# Board_R2.net
KiCad netlist of a schematic drawn in EAGLE
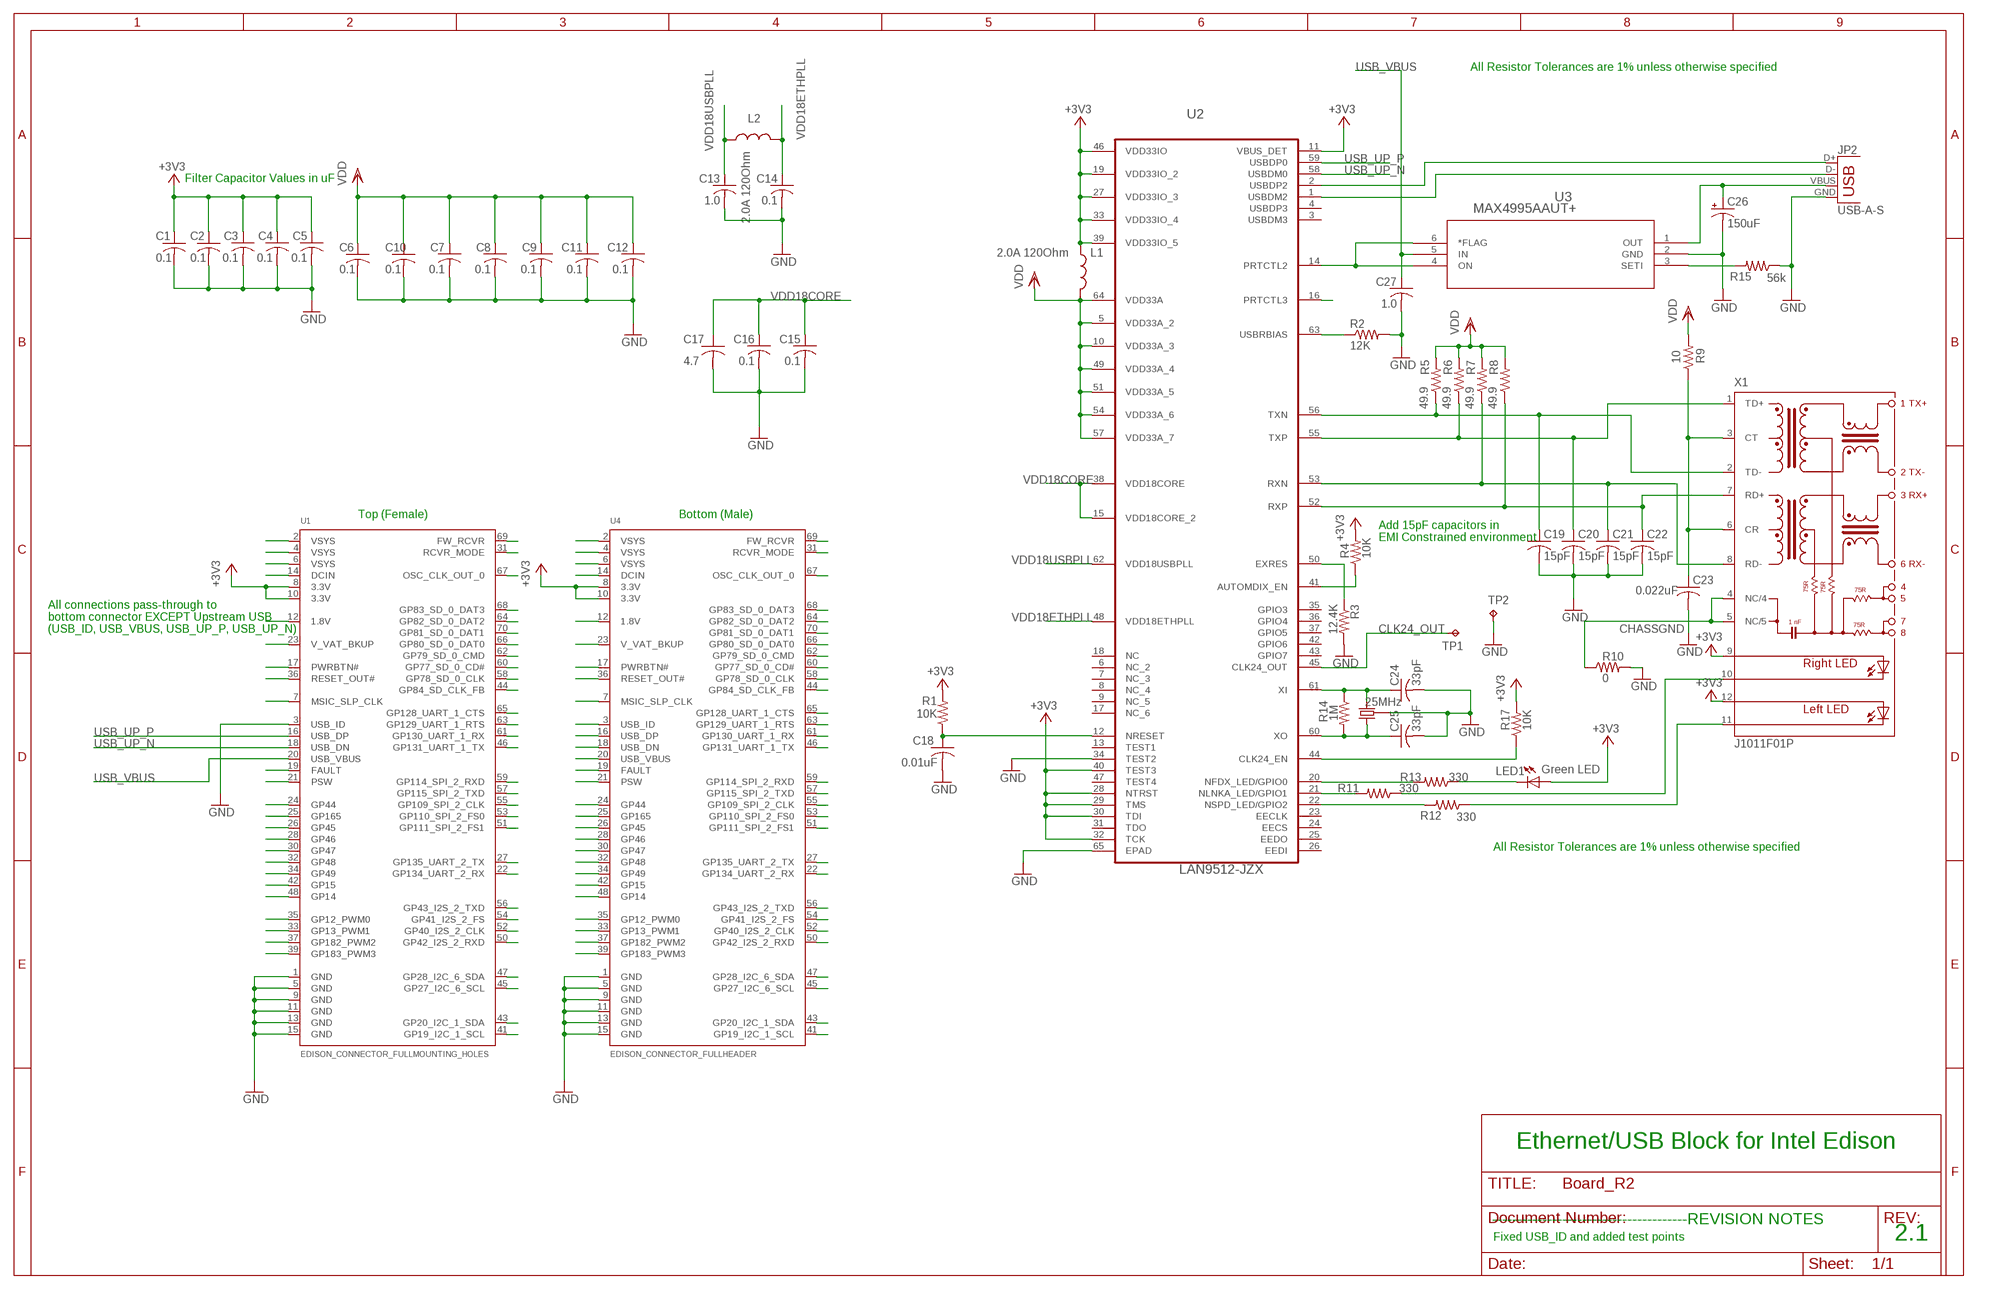
[diagram p0: schematic, sheet 1]

(export (version "E")
  (design (tool "Eeschema 10.0.6"))
  (components
    (comp (ref "C1")
      (value "0.1")
      (footprint "eagle-import:C0402K")
      (libsource (lib "eagle-import") (part "C-USC0402K"))
    )
    (comp (ref "C2")
      (value "0.1")
      (footprint "eagle-import:C0402K")
      (libsource (lib "eagle-import") (part "C-USC0402K"))
    )
    (comp (ref "C3")
      (value "0.1")
      (footprint "eagle-import:C0402K")
      (libsource (lib "eagle-import") (part "C-USC0402K"))
    )
    (comp (ref "C4")
      (value "0.1")
      (footprint "eagle-import:C0402K")
      (libsource (lib "eagle-import") (part "C-USC0402K"))
    )
    (comp (ref "C5")
      (value "0.1")
      (footprint "eagle-import:C0402K")
      (libsource (lib "eagle-import") (part "C-USC0402K"))
    )
    (comp (ref "C6")
      (value "0.1")
      (footprint "eagle-import:C0402K")
      (libsource (lib "eagle-import") (part "C-USC0402K"))
    )
    (comp (ref "C7")
      (value "0.1")
      (footprint "eagle-import:C0402K")
      (libsource (lib "eagle-import") (part "C-USC0402K"))
    )
    (comp (ref "C8")
      (value "0.1")
      (footprint "eagle-import:C0402K")
      (libsource (lib "eagle-import") (part "C-USC0402K"))
    )
    (comp (ref "C9")
      (value "0.1")
      (footprint "eagle-import:C0402K")
      (libsource (lib "eagle-import") (part "C-USC0402K"))
    )
    (comp (ref "C10")
      (value "0.1")
      (footprint "eagle-import:C0402K")
      (libsource (lib "eagle-import") (part "C-USC0402K"))
    )
    (comp (ref "C11")
      (value "0.1")
      (footprint "eagle-import:C0402K")
      (libsource (lib "eagle-import") (part "C-USC0402K"))
    )
    (comp (ref "C12")
      (value "0.1")
      (footprint "eagle-import:C0402K")
      (libsource (lib "eagle-import") (part "C-USC0402K"))
    )
    (comp (ref "C13")
      (value "1.0")
      (footprint "eagle-import:C0402K")
      (libsource (lib "eagle-import") (part "C-USC0402K"))
    )
    (comp (ref "C14")
      (value "0.1")
      (footprint "eagle-import:C0402K")
      (libsource (lib "eagle-import") (part "C-USC0402K"))
    )
    (comp (ref "C15")
      (value "0.1")
      (footprint "eagle-import:C0402K")
      (libsource (lib "eagle-import") (part "C-USC0402K"))
    )
    (comp (ref "C16")
      (value "0.1")
      (footprint "eagle-import:C0402K")
      (libsource (lib "eagle-import") (part "C-USC0402K"))
    )
    (comp (ref "C17")
      (value "4.7")
      (footprint "eagle-import:C0603K")
      (libsource (lib "eagle-import") (part "C-USC0603K"))
    )
    (comp (ref "C18")
      (value "0.01uF")
      (footprint "eagle-import:C0603K")
      (libsource (lib "eagle-import") (part "C-USC0603K"))
    )
    (comp (ref "C19")
      (value "15pF")
      (footprint "eagle-import:C0402")
      (libsource (lib "eagle-import") (part "C-USC0402"))
    )
    (comp (ref "C20")
      (value "15pF")
      (footprint "eagle-import:C0402")
      (libsource (lib "eagle-import") (part "C-USC0402"))
    )
    (comp (ref "C21")
      (value "15pF")
      (footprint "eagle-import:C0402")
      (libsource (lib "eagle-import") (part "C-USC0402"))
    )
    (comp (ref "C22")
      (value "15pF")
      (footprint "eagle-import:C0402")
      (libsource (lib "eagle-import") (part "C-USC0402"))
    )
    (comp (ref "C23")
      (value "0.022uF")
      (footprint "eagle-import:C0805")
      (libsource (lib "eagle-import") (part "resistor_C-USC0805"))
    )
    (comp (ref "C24")
      (value "33pF")
      (footprint "eagle-import:C0402")
      (libsource (lib "eagle-import") (part "C-USC0402"))
    )
    (comp (ref "C25")
      (value "33pF")
      (footprint "eagle-import:C0402")
      (libsource (lib "eagle-import") (part "C-USC0402"))
    )
    (comp (ref "C26")
      (value "150uF")
      (footprint "eagle-import:PANASONIC_E")
      (libsource (lib "eagle-import") (part "CAP_POLE"))
    )
    (comp (ref "C27")
      (value "1.0")
      (footprint "eagle-import:C0402K")
      (libsource (lib "eagle-import") (part "C-USC0402K"))
    )
    (comp (ref "JP2")
      (value "USB-A-S")
      (footprint "eagle-import:USB-A-S")
      (libsource (lib "eagle-import") (part "USB-A-S"))
    )
    (comp (ref "L1")
      (value "2.0A 120Ohm")
      (footprint "eagle-import:L0603")
      (libsource (lib "eagle-import") (part "L-US0603"))
    )
    (comp (ref "L2")
      (value "2.0A 120Ohm")
      (footprint "eagle-import:L0603")
      (libsource (lib "eagle-import") (part "L-US0603"))
    )
    (comp (ref "LED1")
      (value "Green LED")
      (footprint "eagle-import:CHIP-LED0805")
      (libsource (lib "eagle-import") (part "LEDCHIP-LED0805"))
    )
    (comp (ref "R1")
      (value "10K")
      (footprint "eagle-import:R0603")
      (libsource (lib "eagle-import") (part "resistor_R-US_R0603"))
    )
    (comp (ref "R2")
      (value "12K")
      (footprint "eagle-import:R0603")
      (libsource (lib "eagle-import") (part "resistor_R-US_R0603"))
    )
    (comp (ref "R3")
      (value "12.4K")
      (footprint "eagle-import:R0603")
      (libsource (lib "eagle-import") (part "resistor_R-US_R0603"))
    )
    (comp (ref "R4")
      (value "10K")
      (footprint "eagle-import:R0603")
      (libsource (lib "eagle-import") (part "resistor_R-US_R0603"))
    )
    (comp (ref "R5")
      (value "49.9")
      (footprint "eagle-import:R0402")
      (libsource (lib "eagle-import") (part "resistor_R-US_R0402"))
    )
    (comp (ref "R6")
      (value "49.9")
      (footprint "eagle-import:R0402")
      (libsource (lib "eagle-import") (part "resistor_R-US_R0402"))
    )
    (comp (ref "R7")
      (value "49.9")
      (footprint "eagle-import:R0402")
      (libsource (lib "eagle-import") (part "resistor_R-US_R0402"))
    )
    (comp (ref "R8")
      (value "49.9")
      (footprint "eagle-import:R0402")
      (libsource (lib "eagle-import") (part "resistor_R-US_R0402"))
    )
    (comp (ref "R9")
      (value "10")
      (footprint "eagle-import:R0402")
      (libsource (lib "eagle-import") (part "resistor_R-US_R0402"))
    )
    (comp (ref "R10")
      (value "0")
      (footprint "eagle-import:R1210")
      (libsource (lib "eagle-import") (part "resistor_R-US_R1210"))
    )
    (comp (ref "R11")
      (value "330")
      (footprint "eagle-import:R0402")
      (libsource (lib "eagle-import") (part "resistor_R-US_R0402"))
    )
    (comp (ref "R12")
      (value "330")
      (footprint "eagle-import:R0402")
      (libsource (lib "eagle-import") (part "resistor_R-US_R0402"))
    )
    (comp (ref "R13")
      (value "330")
      (footprint "eagle-import:R0402")
      (libsource (lib "eagle-import") (part "resistor_R-US_R0402"))
    )
    (comp (ref "R14")
      (value "1M")
      (footprint "eagle-import:R0402")
      (libsource (lib "eagle-import") (part "resistor_R-US_R0402"))
    )
    (comp (ref "R15")
      (value "56k")
      (footprint "eagle-import:R0603")
      (libsource (lib "eagle-import") (part "R-US_R0603"))
    )
    (comp (ref "R17")
      (value "10K")
      (footprint "eagle-import:R0603")
      (libsource (lib "eagle-import") (part "resistor_R-US_R0603"))
    )
    (comp (ref "TP1")
      (value "TPTP20R")
      (footprint "eagle-import:TP20R")
      (libsource (lib "eagle-import") (part "TPTP20R"))
    )
    (comp (ref "TP2")
      (value "TPTP20R")
      (footprint "eagle-import:TP20R")
      (libsource (lib "eagle-import") (part "TPTP20R"))
    )
    (comp (ref "U$1")
      (value "25MHz")
      (footprint "eagle-import:CRYSTAL-SMD-5X3")
      (libsource (lib "eagle-import") (part "CRYSTAL-GROUNDED"))
    )
    (comp (ref "U1")
      (value "EDISON_CONNECTOR_FULLMOUNTING_HOLES")
      (footprint "eagle-import:EDISON_DAUGHTER")
      (libsource (lib "eagle-import") (part "EDISON_CONNECTOR_FULLMOUNTING_HOLES"))
    )
    (comp (ref "U2")
      (value "LAN9512-JZX")
      (footprint "eagle-import:QFN50P900X900X100-65N")
      (libsource (lib "eagle-import") (part "LAN9512-JZX"))
    )
    (comp (ref "U3")
      (value "MAX4995AAUT+")
      (footprint "eagle-import:21-0058I")
      (fields (field (name "MANUFACTURER_PART_NUMBER") "max4995aaut+"))
      (libsource (lib "eagle-import") (part "MAX4995AAUT+"))
    )
    (comp (ref "U4")
      (value "EDISON_CONNECTOR_FULLHEADER")
      (footprint "eagle-import:DF40C-70DP-0.4(51)")
      (libsource (lib "eagle-import") (part "EDISON_CONNECTOR_FULLHEADER"))
    )
    (comp (ref "X1")
      (value "J1011F01P")
      (footprint "eagle-import:J1")
      (libsource (lib "eagle-import") (part "J1011F01P"))
    )
  )
  (nets
    (net (code "1") (name "+3V3") (class "Default")
      (node (ref "C1") (pin "1") (pinfunction "1_1") (pintype "passive"))
      (node (ref "C2") (pin "1") (pinfunction "1_1") (pintype "passive"))
      (node (ref "C3") (pin "1") (pinfunction "1_1") (pintype "passive"))
      (node (ref "C4") (pin "1") (pinfunction "1_1") (pintype "passive"))
      (node (ref "C5") (pin "1") (pinfunction "1_1") (pintype "passive"))
      (node (ref "L1") (pin "1") (pinfunction "1_1") (pintype "passive"))
      (node (ref "LED1") (pin "A") (pinfunction "A_A") (pintype "passive"))
      (node (ref "R1") (pin "2") (pinfunction "2_2") (pintype "passive"))
      (node (ref "R17") (pin "2") (pinfunction "2_2") (pintype "passive"))
      (node (ref "R4") (pin "2") (pinfunction "2_2") (pintype "passive"))
      (node (ref "U1") (pin "10") (pinfunction "3.3V_10") (pintype "bidirectional"))
      (node (ref "U1") (pin "8") (pinfunction "3.3V_8") (pintype "bidirectional"))
      (node (ref "U2") (pin "11") (pinfunction "VBUS_DET_11") (pintype "power_in"))
      (node (ref "U2") (pin "19") (pinfunction "VDD33IO_2_19") (pintype "power_in"))
      (node (ref "U2") (pin "27") (pinfunction "VDD33IO_3_27") (pintype "power_in"))
      (node (ref "U2") (pin "28") (pinfunction "NTRST_28") (pintype "passive"))
      (node (ref "U2") (pin "29") (pinfunction "TMS_29") (pintype "passive"))
      (node (ref "U2") (pin "30") (pinfunction "TDI_30") (pintype "passive"))
      (node (ref "U2") (pin "32") (pinfunction "TCK_32") (pintype "passive"))
      (node (ref "U2") (pin "33") (pinfunction "VDD33IO_4_33") (pintype "power_in"))
      (node (ref "U2") (pin "39") (pinfunction "VDD33IO_5_39") (pintype "power_in"))
      (node (ref "U2") (pin "40") (pinfunction "TEST3_40") (pintype "passive"))
      (node (ref "U2") (pin "46") (pinfunction "VDD33IO_46") (pintype "power_in"))
      (node (ref "U4") (pin "10") (pinfunction "3.3V_10") (pintype "bidirectional"))
      (node (ref "U4") (pin "8") (pinfunction "3.3V_8") (pintype "bidirectional"))
      (node (ref "X1") (pin "12") (pinfunction "AL_12") (pintype "passive"))
      (node (ref "X1") (pin "9") (pinfunction "A-R_9") (pintype "passive"))
    )
    (net (code "2") (name "/CHASSGND") (class "Default")
      (node (ref "R10") (pin "1") (pinfunction "1_1") (pintype "passive"))
      (node (ref "X1") (pin "4") (pinfunction "NC/4_4") (pintype "input"))
      (node (ref "X1") (pin "5") (pinfunction "NC/5_5") (pintype "input"))
    )
    (net (code "3") (name "/CLK24_OUT") (class "Default")
      (node (ref "TP1") (pin "TP") (pinfunction "TP_TP") (pintype "input"))
      (node (ref "U2") (pin "45") (pinfunction "CLK24_OUT_45") (pintype "passive"))
    )
    (net (code "4") (name "/P2") (class "Default")
      (node (ref "U1") (pin "2") (pinfunction "VSYS_2") (pintype "bidirectional"))
      (node (ref "U4") (pin "2") (pinfunction "VSYS_2") (pintype "bidirectional"))
    )
    (net (code "5") (name "/P4") (class "Default")
      (node (ref "U1") (pin "4") (pinfunction "VSYS_4") (pintype "bidirectional"))
      (node (ref "U4") (pin "4") (pinfunction "VSYS_4") (pintype "bidirectional"))
    )
    (net (code "6") (name "/P6") (class "Default")
      (node (ref "U1") (pin "6") (pinfunction "VSYS_6") (pintype "bidirectional"))
      (node (ref "U4") (pin "6") (pinfunction "VSYS_6") (pintype "bidirectional"))
    )
    (net (code "7") (name "/P7") (class "Default")
      (node (ref "U1") (pin "7") (pinfunction "MSIC_SLP_CLK_7") (pintype "bidirectional"))
      (node (ref "U4") (pin "7") (pinfunction "MSIC_SLP_CLK_7") (pintype "bidirectional"))
    )
    (net (code "8") (name "/P12") (class "Default")
      (node (ref "U1") (pin "12") (pinfunction "1.8V_12") (pintype "bidirectional"))
      (node (ref "U4") (pin "12") (pinfunction "1.8V_12") (pintype "bidirectional"))
    )
    (net (code "9") (name "/P14") (class "Default")
      (node (ref "U1") (pin "14") (pinfunction "DCIN_14") (pintype "bidirectional"))
      (node (ref "U4") (pin "14") (pinfunction "DCIN_14") (pintype "bidirectional"))
    )
    (net (code "10") (name "/P17") (class "Default")
      (node (ref "U1") (pin "17") (pinfunction "PWRBTN#_17") (pintype "bidirectional"))
      (node (ref "U4") (pin "17") (pinfunction "PWRBTN#_17") (pintype "bidirectional"))
    )
    (net (code "11") (name "/P19") (class "Default")
      (node (ref "U1") (pin "19") (pinfunction "FAULT_19") (pintype "bidirectional"))
      (node (ref "U4") (pin "19") (pinfunction "FAULT_19") (pintype "bidirectional"))
    )
    (net (code "12") (name "/P21") (class "Default")
      (node (ref "U1") (pin "21") (pinfunction "PSW_21") (pintype "bidirectional"))
      (node (ref "U4") (pin "21") (pinfunction "PSW_21") (pintype "bidirectional"))
    )
    (net (code "13") (name "/P22") (class "Default")
      (node (ref "U1") (pin "22") (pinfunction "GP134_UART_2_RX_22") (pintype "bidirectional"))
      (node (ref "U4") (pin "22") (pinfunction "GP134_UART_2_RX_22") (pintype "bidirectional"))
    )
    (net (code "14") (name "/P23") (class "Default")
      (node (ref "U1") (pin "23") (pinfunction "V_VAT_BKUP_23") (pintype "bidirectional"))
      (node (ref "U4") (pin "23") (pinfunction "V_VAT_BKUP_23") (pintype "bidirectional"))
    )
    (net (code "15") (name "/P24") (class "Default")
      (node (ref "U1") (pin "24") (pinfunction "GP44_24") (pintype "bidirectional"))
      (node (ref "U4") (pin "24") (pinfunction "GP44_24") (pintype "bidirectional"))
    )
    (net (code "16") (name "/P25") (class "Default")
      (node (ref "U1") (pin "25") (pinfunction "GP165_25") (pintype "bidirectional"))
      (node (ref "U4") (pin "25") (pinfunction "GP165_25") (pintype "bidirectional"))
    )
    (net (code "17") (name "/P26") (class "Default")
      (node (ref "U1") (pin "26") (pinfunction "GP45_26") (pintype "bidirectional"))
      (node (ref "U4") (pin "26") (pinfunction "GP45_26") (pintype "bidirectional"))
    )
    (net (code "18") (name "/P27") (class "Default")
      (node (ref "U1") (pin "27") (pinfunction "GP135_UART_2_TX_27") (pintype "bidirectional"))
      (node (ref "U4") (pin "27") (pinfunction "GP135_UART_2_TX_27") (pintype "bidirectional"))
    )
    (net (code "19") (name "/P28") (class "Default")
      (node (ref "U1") (pin "28") (pinfunction "GP46_28") (pintype "bidirectional"))
      (node (ref "U4") (pin "28") (pinfunction "GP46_28") (pintype "bidirectional"))
    )
    (net (code "20") (name "/P30") (class "Default")
      (node (ref "U1") (pin "30") (pinfunction "GP47_30") (pintype "bidirectional"))
      (node (ref "U4") (pin "30") (pinfunction "GP47_30") (pintype "bidirectional"))
    )
    (net (code "21") (name "/P31") (class "Default")
      (node (ref "U1") (pin "31") (pinfunction "RCVR_MODE_31") (pintype "bidirectional"))
      (node (ref "U4") (pin "31") (pinfunction "RCVR_MODE_31") (pintype "bidirectional"))
    )
    (net (code "22") (name "/P32") (class "Default")
      (node (ref "U1") (pin "32") (pinfunction "GP48_32") (pintype "bidirectional"))
      (node (ref "U4") (pin "32") (pinfunction "GP48_32") (pintype "bidirectional"))
    )
    (net (code "23") (name "/P33") (class "Default")
      (node (ref "U1") (pin "33") (pinfunction "GP13_PWM1_33") (pintype "bidirectional"))
      (node (ref "U4") (pin "33") (pinfunction "GP13_PWM1_33") (pintype "bidirectional"))
    )
    (net (code "24") (name "/P34") (class "Default")
      (node (ref "U1") (pin "34") (pinfunction "GP49_34") (pintype "bidirectional"))
      (node (ref "U4") (pin "34") (pinfunction "GP49_34") (pintype "bidirectional"))
    )
    (net (code "25") (name "/P35") (class "Default")
      (node (ref "U1") (pin "35") (pinfunction "GP12_PWM0_35") (pintype "bidirectional"))
      (node (ref "U4") (pin "35") (pinfunction "GP12_PWM0_35") (pintype "bidirectional"))
    )
    (net (code "26") (name "/P36") (class "Default")
      (node (ref "U1") (pin "36") (pinfunction "RESET_OUT#_36") (pintype "bidirectional"))
      (node (ref "U4") (pin "36") (pinfunction "RESET_OUT#_36") (pintype "bidirectional"))
    )
    (net (code "27") (name "/P37") (class "Default")
      (node (ref "U1") (pin "37") (pinfunction "GP182_PWM2_37") (pintype "bidirectional"))
      (node (ref "U4") (pin "37") (pinfunction "GP182_PWM2_37") (pintype "bidirectional"))
    )
    (net (code "28") (name "/P39") (class "Default")
      (node (ref "U1") (pin "39") (pinfunction "GP183_PWM3_39") (pintype "bidirectional"))
      (node (ref "U4") (pin "39") (pinfunction "GP183_PWM3_39") (pintype "bidirectional"))
    )
    (net (code "29") (name "/P41") (class "Default")
      (node (ref "U1") (pin "41") (pinfunction "GP19_I2C_1_SCL_41") (pintype "bidirectional"))
      (node (ref "U4") (pin "41") (pinfunction "GP19_I2C_1_SCL_41") (pintype "bidirectional"))
    )
    (net (code "30") (name "/P42") (class "Default")
      (node (ref "U1") (pin "42") (pinfunction "GP15_42") (pintype "bidirectional"))
      (node (ref "U4") (pin "42") (pinfunction "GP15_42") (pintype "bidirectional"))
    )
    (net (code "31") (name "/P43") (class "Default")
      (node (ref "U1") (pin "43") (pinfunction "GP20_I2C_1_SDA_43") (pintype "bidirectional"))
      (node (ref "U4") (pin "43") (pinfunction "GP20_I2C_1_SDA_43") (pintype "bidirectional"))
    )
    (net (code "32") (name "/P44") (class "Default")
      (node (ref "U1") (pin "44") (pinfunction "GP84_SD_CLK_FB_44") (pintype "bidirectional"))
      (node (ref "U4") (pin "44") (pinfunction "GP84_SD_CLK_FB_44") (pintype "bidirectional"))
    )
    (net (code "33") (name "/P45") (class "Default")
      (node (ref "U1") (pin "45") (pinfunction "GP27_I2C_6_SCL_45") (pintype "bidirectional"))
      (node (ref "U4") (pin "45") (pinfunction "GP27_I2C_6_SCL_45") (pintype "bidirectional"))
    )
    (net (code "34") (name "/P46") (class "Default")
      (node (ref "U1") (pin "46") (pinfunction "GP131_UART_1_TX_46") (pintype "bidirectional"))
      (node (ref "U4") (pin "46") (pinfunction "GP131_UART_1_TX_46") (pintype "bidirectional"))
    )
    (net (code "35") (name "/P47") (class "Default")
      (node (ref "U1") (pin "47") (pinfunction "GP28_I2C_6_SDA_47") (pintype "bidirectional"))
      (node (ref "U4") (pin "47") (pinfunction "GP28_I2C_6_SDA_47") (pintype "bidirectional"))
    )
    (net (code "36") (name "/P48") (class "Default")
      (node (ref "U1") (pin "48") (pinfunction "GP14_48") (pintype "bidirectional"))
      (node (ref "U4") (pin "48") (pinfunction "GP14_48") (pintype "bidirectional"))
    )
    (net (code "37") (name "/P50") (class "Default")
      (node (ref "U1") (pin "50") (pinfunction "GP42_I2S_2_RXD_50") (pintype "bidirectional"))
      (node (ref "U4") (pin "50") (pinfunction "GP42_I2S_2_RXD_50") (pintype "bidirectional"))
    )
    (net (code "38") (name "/P51") (class "Default")
      (node (ref "U1") (pin "51") (pinfunction "GP111_SPI_2_FS1_51") (pintype "bidirectional"))
      (node (ref "U4") (pin "51") (pinfunction "GP111_SPI_2_FS1_51") (pintype "bidirectional"))
    )
    (net (code "39") (name "/P52") (class "Default")
      (node (ref "U1") (pin "52") (pinfunction "GP40_I2S_2_CLK_52") (pintype "bidirectional"))
      (node (ref "U4") (pin "52") (pinfunction "GP40_I2S_2_CLK_52") (pintype "bidirectional"))
    )
    (net (code "40") (name "/P53") (class "Default")
      (node (ref "U1") (pin "53") (pinfunction "GP110_SPI_2_FS0_53") (pintype "bidirectional"))
      (node (ref "U4") (pin "53") (pinfunction "GP110_SPI_2_FS0_53") (pintype "bidirectional"))
    )
    (net (code "41") (name "/P54") (class "Default")
      (node (ref "U1") (pin "54") (pinfunction "GP41_I2S_2_FS_54") (pintype "bidirectional"))
      (node (ref "U4") (pin "54") (pinfunction "GP41_I2S_2_FS_54") (pintype "bidirectional"))
    )
    (net (code "42") (name "/P55") (class "Default")
      (node (ref "U1") (pin "55") (pinfunction "GP109_SPI_2_CLK_55") (pintype "bidirectional"))
      (node (ref "U4") (pin "55") (pinfunction "GP109_SPI_2_CLK_55") (pintype "bidirectional"))
    )
    (net (code "43") (name "/P56") (class "Default")
      (node (ref "U1") (pin "56") (pinfunction "GP43_I2S_2_TXD_56") (pintype "bidirectional"))
      (node (ref "U4") (pin "56") (pinfunction "GP43_I2S_2_TXD_56") (pintype "bidirectional"))
    )
    (net (code "44") (name "/P57") (class "Default")
      (node (ref "U1") (pin "57") (pinfunction "GP115_SPI_2_TXD_57") (pintype "bidirectional"))
      (node (ref "U4") (pin "57") (pinfunction "GP115_SPI_2_TXD_57") (pintype "bidirectional"))
    )
    (net (code "45") (name "/P58") (class "Default")
      (node (ref "U1") (pin "58") (pinfunction "GP78_SD_0_CLK_58") (pintype "bidirectional"))
      (node (ref "U4") (pin "58") (pinfunction "GP78_SD_0_CLK_58") (pintype "bidirectional"))
    )
    (net (code "46") (name "/P59") (class "Default")
      (node (ref "U1") (pin "59") (pinfunction "GP114_SPI_2_RXD_59") (pintype "bidirectional"))
      (node (ref "U4") (pin "59") (pinfunction "GP114_SPI_2_RXD_59") (pintype "bidirectional"))
    )
    (net (code "47") (name "/P60") (class "Default")
      (node (ref "U1") (pin "60") (pinfunction "GP77_SD_0_CD#_60") (pintype "bidirectional"))
      (node (ref "U4") (pin "60") (pinfunction "GP77_SD_0_CD#_60") (pintype "bidirectional"))
    )
    (net (code "48") (name "/P61") (class "Default")
      (node (ref "U1") (pin "61") (pinfunction "GP130_UART_1_RX_61") (pintype "bidirectional"))
      (node (ref "U4") (pin "61") (pinfunction "GP130_UART_1_RX_61") (pintype "bidirectional"))
    )
    (net (code "49") (name "/P62") (class "Default")
      (node (ref "U1") (pin "62") (pinfunction "GP79_SD_0_CMD_62") (pintype "bidirectional"))
      (node (ref "U4") (pin "62") (pinfunction "GP79_SD_0_CMD_62") (pintype "bidirectional"))
    )
    (net (code "50") (name "/P63") (class "Default")
      (node (ref "U1") (pin "63") (pinfunction "GP129_UART_1_RTS_63") (pintype "bidirectional"))
      (node (ref "U4") (pin "63") (pinfunction "GP129_UART_1_RTS_63") (pintype "bidirectional"))
    )
    (net (code "51") (name "/P64") (class "Default")
      (node (ref "U1") (pin "64") (pinfunction "GP82_SD_0_DAT2_64") (pintype "bidirectional"))
      (node (ref "U4") (pin "64") (pinfunction "GP82_SD_0_DAT2_64") (pintype "bidirectional"))
    )
    (net (code "52") (name "/P65") (class "Default")
      (node (ref "U1") (pin "65") (pinfunction "GP128_UART_1_CTS_65") (pintype "bidirectional"))
      (node (ref "U4") (pin "65") (pinfunction "GP128_UART_1_CTS_65") (pintype "bidirectional"))
    )
    (net (code "53") (name "/P66") (class "Default")
      (node (ref "U1") (pin "66") (pinfunction "GP80_SD_0_DAT0_66") (pintype "bidirectional"))
      (node (ref "U4") (pin "66") (pinfunction "GP80_SD_0_DAT0_66") (pintype "bidirectional"))
    )
    (net (code "54") (name "/P67") (class "Default")
      (node (ref "U1") (pin "67") (pinfunction "OSC_CLK_OUT_0_67") (pintype "bidirectional"))
      (node (ref "U4") (pin "67") (pinfunction "OSC_CLK_OUT_0_67") (pintype "bidirectional"))
    )
    (net (code "55") (name "/P68") (class "Default")
      (node (ref "U1") (pin "68") (pinfunction "GP83_SD_0_DAT3_68") (pintype "bidirectional"))
      (node (ref "U4") (pin "68") (pinfunction "GP83_SD_0_DAT3_68") (pintype "bidirectional"))
    )
    (net (code "56") (name "/P69") (class "Default")
      (node (ref "U1") (pin "69") (pinfunction "FW_RCVR_69") (pintype "bidirectional"))
      (node (ref "U4") (pin "69") (pinfunction "FW_RCVR_69") (pintype "bidirectional"))
    )
    (net (code "57") (name "/P70") (class "Default")
      (node (ref "U1") (pin "70") (pinfunction "GP81_SD_0_DAT1_70") (pintype "bidirectional"))
      (node (ref "U4") (pin "70") (pinfunction "GP81_SD_0_DAT1_70") (pintype "bidirectional"))
    )
    (net (code "58") (name "/USB_UP_N") (class "Default")
      (node (ref "U1") (pin "18") (pinfunction "USB_DN_18") (pintype "bidirectional"))
      (node (ref "U2") (pin "58") (pinfunction "USBDM0_58") (pintype "passive"))
    )
    (net (code "59") (name "/USB_UP_P") (class "Default")
      (node (ref "U1") (pin "16") (pinfunction "USB_DP_16") (pintype "bidirectional"))
      (node (ref "U2") (pin "59") (pinfunction "USBDP0_59") (pintype "passive"))
    )
    (net (code "60") (name "/USB_VBUS") (class "Default")
      (node (ref "C27") (pin "1") (pinfunction "1_1") (pintype "passive"))
      (node (ref "U1") (pin "20") (pinfunction "USB_VBUS_20") (pintype "bidirectional"))
      (node (ref "U3") (pin "5") (pinfunction "IN_5") (pintype "input"))
      (node (ref "U4") (pin "20") (pinfunction "USB_VBUS_20") (pintype "bidirectional"))
    )
    (net (code "61") (name "/VDD18CORE") (class "Default")
      (node (ref "C15") (pin "1") (pinfunction "1_1") (pintype "passive"))
      (node (ref "C16") (pin "1") (pinfunction "1_1") (pintype "passive"))
      (node (ref "C17") (pin "1") (pinfunction "1_1") (pintype "passive"))
      (node (ref "U2") (pin "15") (pinfunction "VDD18CORE_2_15") (pintype "power_in"))
      (node (ref "U2") (pin "38") (pinfunction "VDD18CORE_38") (pintype "power_in"))
    )
    (net (code "62") (name "/VDD18ETHPLL") (class "Default")
      (node (ref "C14") (pin "1") (pinfunction "1_1") (pintype "passive"))
      (node (ref "L2") (pin "2") (pinfunction "2_2") (pintype "passive"))
      (node (ref "U2") (pin "48") (pinfunction "VDD18ETHPLL_48") (pintype "power_in"))
    )
    (net (code "63") (name "/VDD18USBPLL") (class "Default")
      (node (ref "C13") (pin "1") (pinfunction "1_1") (pintype "passive"))
      (node (ref "L2") (pin "1") (pinfunction "1_1") (pintype "passive"))
      (node (ref "U2") (pin "62") (pinfunction "VDD18USBPLL_62") (pintype "power_in"))
    )
    (net (code "64") (name "GND") (class "Default")
      (node (ref "C1") (pin "2") (pinfunction "2_2") (pintype "passive"))
      (node (ref "C10") (pin "2") (pinfunction "2_2") (pintype "passive"))
      (node (ref "C11") (pin "2") (pinfunction "2_2") (pintype "passive"))
      (node (ref "C12") (pin "2") (pinfunction "2_2") (pintype "passive"))
      (node (ref "C13") (pin "2") (pinfunction "2_2") (pintype "passive"))
      (node (ref "C14") (pin "2") (pinfunction "2_2") (pintype "passive"))
      (node (ref "C15") (pin "2") (pinfunction "2_2") (pintype "passive"))
      (node (ref "C16") (pin "2") (pinfunction "2_2") (pintype "passive"))
      (node (ref "C17") (pin "2") (pinfunction "2_2") (pintype "passive"))
      (node (ref "C18") (pin "2") (pinfunction "2_2") (pintype "passive"))
      (node (ref "C19") (pin "2") (pinfunction "2_2") (pintype "passive"))
      (node (ref "C2") (pin "2") (pinfunction "2_2") (pintype "passive"))
      (node (ref "C20") (pin "2") (pinfunction "2_2") (pintype "passive"))
      (node (ref "C21") (pin "2") (pinfunction "2_2") (pintype "passive"))
      (node (ref "C22") (pin "2") (pinfunction "2_2") (pintype "passive"))
      (node (ref "C23") (pin "2") (pinfunction "2_2") (pintype "passive"))
      (node (ref "C24") (pin "2") (pinfunction "2_2") (pintype "passive"))
      (node (ref "C25") (pin "2") (pinfunction "2_2") (pintype "passive"))
      (node (ref "C26") (pin "-") (pinfunction "-_-") (pintype "passive"))
      (node (ref "C27") (pin "2") (pinfunction "2_2") (pintype "passive"))
      (node (ref "C3") (pin "2") (pinfunction "2_2") (pintype "passive"))
      (node (ref "C4") (pin "2") (pinfunction "2_2") (pintype "passive"))
      (node (ref "C5") (pin "2") (pinfunction "2_2") (pintype "passive"))
      (node (ref "C6") (pin "2") (pinfunction "2_2") (pintype "passive"))
      (node (ref "C7") (pin "2") (pinfunction "2_2") (pintype "passive"))
      (node (ref "C8") (pin "2") (pinfunction "2_2") (pintype "passive"))
      (node (ref "C9") (pin "2") (pinfunction "2_2") (pintype "passive"))
      (node (ref "JP2") (pin "GND") (pinfunction "GND_GND") (pintype "bidirectional"))
      (node (ref "R10") (pin "2") (pinfunction "2_2") (pintype "passive"))
      (node (ref "R15") (pin "1") (pinfunction "1_1") (pintype "passive"))
      (node (ref "R2") (pin "2") (pinfunction "2_2") (pintype "passive"))
      (node (ref "R3") (pin "2") (pinfunction "2_2") (pintype "passive"))
      (node (ref "TP2") (pin "TP") (pinfunction "TP_TP") (pintype "input"))
      (node (ref "U$1") (pin "2") (pinfunction "3_2") (pintype "passive"))
      (node (ref "U$1") (pin "4") (pinfunction "3_4") (pintype "passive"))
      (node (ref "U1") (pin "1") (pinfunction "GND_1") (pintype "bidirectional"))
      (node (ref "U1") (pin "11") (pinfunction "GND_11") (pintype "bidirectional"))
      (node (ref "U1") (pin "13") (pinfunction "GND_13") (pintype "bidirectional"))
      (node (ref "U1") (pin "15") (pinfunction "GND_15") (pintype "bidirectional"))
      (node (ref "U1") (pin "3") (pinfunction "USB_ID_3") (pintype "bidirectional"))
      (node (ref "U1") (pin "5") (pinfunction "GND_5") (pintype "bidirectional"))
      (node (ref "U1") (pin "9") (pinfunction "GND_9") (pintype "bidirectional"))
      (node (ref "U2") (pin "34") (pinfunction "TEST2_34") (pintype "passive"))
      (node (ref "U2") (pin "65") (pinfunction "EPAD_65") (pintype "passive"))
      (node (ref "U3") (pin "2") (pinfunction "GND_2") (pintype "power_in"))
      (node (ref "U4") (pin "1") (pinfunction "GND_1") (pintype "bidirectional"))
      (node (ref "U4") (pin "11") (pinfunction "GND_11") (pintype "bidirectional"))
      (node (ref "U4") (pin "13") (pinfunction "GND_13") (pintype "bidirectional"))
      (node (ref "U4") (pin "15") (pinfunction "GND_15") (pintype "bidirectional"))
      (node (ref "U4") (pin "5") (pinfunction "GND_5") (pintype "bidirectional"))
      (node (ref "U4") (pin "9") (pinfunction "GND_9") (pintype "bidirectional"))
    )
    (net (code "65") (name "Net-(LED1-PadC)") (class "Default")
      (node (ref "LED1") (pin "C") (pinfunction "C_C") (pintype "passive"))
      (node (ref "R13") (pin "1") (pinfunction "1_1") (pintype "passive"))
    )
    (net (code "66") (name "Net-(U$1-1)") (class "Default")
      (node (ref "C25") (pin "1") (pinfunction "1_1") (pintype "passive"))
      (node (ref "R14") (pin "2") (pinfunction "2_2") (pintype "passive"))
      (node (ref "U$1") (pin "3") (pinfunction "1_3") (pintype "passive"))
      (node (ref "U2") (pin "60") (pinfunction "XO_60") (pintype "passive"))
    )
    (net (code "67") (name "Net-(U$1-2)") (class "Default")
      (node (ref "C24") (pin "1") (pinfunction "1_1") (pintype "passive"))
      (node (ref "R14") (pin "1") (pinfunction "1_1") (pintype "passive"))
      (node (ref "U$1") (pin "1") (pinfunction "2_1") (pintype "passive"))
      (node (ref "U2") (pin "61") (pinfunction "XI_61") (pintype "passive"))
    )
    (net (code "68") (name "Net-(U2-AUTOMDIX_EN)") (class "Default")
      (node (ref "R4") (pin "1") (pinfunction "1_1") (pintype "passive"))
      (node (ref "U2") (pin "41") (pinfunction "AUTOMDIX_EN_41") (pintype "passive"))
    )
    (net (code "69") (name "Net-(U2-CLK24_EN)") (class "Default")
      (node (ref "R17") (pin "1") (pinfunction "1_1") (pintype "passive"))
      (node (ref "U2") (pin "44") (pinfunction "CLK24_EN_44") (pintype "passive"))
    )
    (net (code "70") (name "Net-(U2-EXRES)") (class "Default")
      (node (ref "R3") (pin "1") (pinfunction "1_1") (pintype "passive"))
      (node (ref "U2") (pin "50") (pinfunction "EXRES_50") (pintype "passive"))
    )
    (net (code "71") (name "Net-(U2-NFDX_LED{slash}GPIO0)") (class "Default")
      (node (ref "R13") (pin "2") (pinfunction "2_2") (pintype "passive"))
      (node (ref "U2") (pin "20") (pinfunction "NFDX_LED/GPIO0_20") (pintype "bidirectional"))
    )
    (net (code "72") (name "Net-(U2-NLNKA_LED{slash}GPIO1)") (class "Default")
      (node (ref "R11") (pin "2") (pinfunction "2_2") (pintype "passive"))
      (node (ref "U2") (pin "21") (pinfunction "NLNKA_LED/GPIO1_21") (pintype "bidirectional"))
    )
    (net (code "73") (name "Net-(U2-NRESET)") (class "Default")
      (node (ref "C18") (pin "1") (pinfunction "1_1") (pintype "passive"))
      (node (ref "R1") (pin "1") (pinfunction "1_1") (pintype "passive"))
      (node (ref "U2") (pin "12") (pinfunction "NRESET_12") (pintype "passive"))
    )
    (net (code "74") (name "Net-(U2-NSPD_LED{slash}GPIO2)") (class "Default")
      (node (ref "R12") (pin "2") (pinfunction "2_2") (pintype "passive"))
      (node (ref "U2") (pin "22") (pinfunction "NSPD_LED/GPIO2_22") (pintype "bidirectional"))
    )
    (net (code "75") (name "Net-(U2-PRTCTL2)") (class "Default")
      (node (ref "U2") (pin "14") (pinfunction "PRTCTL2_14") (pintype "passive"))
      (node (ref "U3") (pin "4") (pinfunction "ON_4") (pintype "input"))
      (node (ref "U3") (pin "6") (pinfunction "*FLAG_6") (pintype "output"))
    )
    (net (code "76") (name "Net-(U2-RXN)") (class "Default")
      (node (ref "C21") (pin "1") (pinfunction "1_1") (pintype "passive"))
      (node (ref "R7") (pin "1") (pinfunction "1_1") (pintype "passive"))
      (node (ref "U2") (pin "53") (pinfunction "RXN_53") (pintype "passive"))
      (node (ref "X1") (pin "8") (pinfunction "RD-_8") (pintype "input"))
    )
    (net (code "77") (name "Net-(U2-RXP)") (class "Default")
      (node (ref "C22") (pin "1") (pinfunction "1_1") (pintype "passive"))
      (node (ref "R8") (pin "1") (pinfunction "1_1") (pintype "passive"))
      (node (ref "U2") (pin "52") (pinfunction "RXP_52") (pintype "passive"))
      (node (ref "X1") (pin "7") (pinfunction "RD+_7") (pintype "input"))
    )
    (net (code "78") (name "Net-(U2-TXN)") (class "Default")
      (node (ref "C19") (pin "1") (pinfunction "1_1") (pintype "passive"))
      (node (ref "R5") (pin "1") (pinfunction "1_1") (pintype "passive"))
      (node (ref "U2") (pin "56") (pinfunction "TXN_56") (pintype "passive"))
      (node (ref "X1") (pin "2") (pinfunction "TD-_2") (pintype "input"))
    )
    (net (code "79") (name "Net-(U2-TXP)") (class "Default")
      (node (ref "C20") (pin "1") (pinfunction "1_1") (pintype "passive"))
      (node (ref "R6") (pin "1") (pinfunction "1_1") (pintype "passive"))
      (node (ref "U2") (pin "55") (pinfunction "TXP_55") (pintype "passive"))
      (node (ref "X1") (pin "1") (pinfunction "TD+_1") (pintype "input"))
    )
    (net (code "80") (name "Net-(U2-USBDM2)") (class "Default")
      (node (ref "JP2") (pin "D-") (pinfunction "D-_D-") (pintype "bidirectional"))
      (node (ref "U2") (pin "1") (pinfunction "USBDM2_1") (pintype "passive"))
    )
    (net (code "81") (name "Net-(U2-USBDP2)") (class "Default")
      (node (ref "JP2") (pin "D+") (pinfunction "D+_D+") (pintype "bidirectional"))
      (node (ref "U2") (pin "2") (pinfunction "USBDP2_2") (pintype "passive"))
    )
    (net (code "82") (name "Net-(U2-USBRBIAS)") (class "Default")
      (node (ref "R2") (pin "1") (pinfunction "1_1") (pintype "passive"))
      (node (ref "U2") (pin "63") (pinfunction "USBRBIAS_63") (pintype "passive"))
    )
    (net (code "83") (name "Net-(U3-OUT)") (class "Default")
      (node (ref "C26") (pin "+") (pinfunction "+_+") (pintype "passive"))
      (node (ref "JP2") (pin "VBUS") (pinfunction "VBUS_VBUS") (pintype "bidirectional"))
      (node (ref "U3") (pin "1") (pinfunction "OUT_1") (pintype "output"))
    )
    (net (code "84") (name "Net-(U3-SETI)") (class "Default")
      (node (ref "R15") (pin "2") (pinfunction "2_2") (pintype "passive"))
      (node (ref "U3") (pin "3") (pinfunction "SETI_3") (pintype "passive"))
    )
    (net (code "85") (name "Net-(X1-C-L)") (class "Default")
      (node (ref "R12") (pin "1") (pinfunction "1_1") (pintype "passive"))
      (node (ref "X1") (pin "11") (pinfunction "C-L_11") (pintype "passive"))
    )
    (net (code "86") (name "Net-(X1-C-R)") (class "Default")
      (node (ref "R11") (pin "1") (pinfunction "1_1") (pintype "passive"))
      (node (ref "X1") (pin "10") (pinfunction "C-R_10") (pintype "passive"))
    )
    (net (code "87") (name "Net-(X1-CR)") (class "Default")
      (node (ref "C23") (pin "1") (pinfunction "1_1") (pintype "passive"))
      (node (ref "R9") (pin "1") (pinfunction "1_1") (pintype "passive"))
      (node (ref "X1") (pin "3") (pinfunction "CT_3") (pintype "input"))
      (node (ref "X1") (pin "6") (pinfunction "CR_6") (pintype "input"))
    )
    (net (code "88") (name "VDD") (class "Default")
      (node (ref "C10") (pin "1") (pinfunction "1_1") (pintype "passive"))
      (node (ref "C11") (pin "1") (pinfunction "1_1") (pintype "passive"))
      (node (ref "C12") (pin "1") (pinfunction "1_1") (pintype "passive"))
      (node (ref "C6") (pin "1") (pinfunction "1_1") (pintype "passive"))
      (node (ref "C7") (pin "1") (pinfunction "1_1") (pintype "passive"))
      (node (ref "C8") (pin "1") (pinfunction "1_1") (pintype "passive"))
      (node (ref "C9") (pin "1") (pinfunction "1_1") (pintype "passive"))
      (node (ref "L1") (pin "2") (pinfunction "2_2") (pintype "passive"))
      (node (ref "R5") (pin "2") (pinfunction "2_2") (pintype "passive"))
      (node (ref "R6") (pin "2") (pinfunction "2_2") (pintype "passive"))
      (node (ref "R7") (pin "2") (pinfunction "2_2") (pintype "passive"))
      (node (ref "R8") (pin "2") (pinfunction "2_2") (pintype "passive"))
      (node (ref "R9") (pin "2") (pinfunction "2_2") (pintype "passive"))
      (node (ref "U2") (pin "10") (pinfunction "VDD33A_3_10") (pintype "power_in"))
      (node (ref "U2") (pin "49") (pinfunction "VDD33A_4_49") (pintype "power_in"))
      (node (ref "U2") (pin "5") (pinfunction "VDD33A_2_5") (pintype "power_in"))
      (node (ref "U2") (pin "51") (pinfunction "VDD33A_5_51") (pintype "power_in"))
      (node (ref "U2") (pin "54") (pinfunction "VDD33A_6_54") (pintype "power_in"))
      (node (ref "U2") (pin "57") (pinfunction "VDD33A_7_57") (pintype "power_in"))
      (node (ref "U2") (pin "64") (pinfunction "VDD33A_64") (pintype "power_in"))
    )
    (net (code "89") (name "unconnected-(U2-EECLK-Pad23)") (class "Default")
      (node (ref "U2") (pin "23") (pinfunction "EECLK_23") (pintype "passive"))
    )
    (net (code "90") (name "unconnected-(U2-EECS-Pad24)") (class "Default")
      (node (ref "U2") (pin "24") (pinfunction "EECS_24") (pintype "passive"))
    )
    (net (code "91") (name "unconnected-(U2-EEDI-Pad26)") (class "Default")
      (node (ref "U2") (pin "26") (pinfunction "EEDI_26") (pintype "passive"))
    )
    (net (code "92") (name "unconnected-(U2-EEDO-Pad25)") (class "Default")
      (node (ref "U2") (pin "25") (pinfunction "EEDO_25") (pintype "passive"))
    )
    (net (code "93") (name "unconnected-(U2-GPIO3-Pad35)") (class "Default")
      (node (ref "U2") (pin "35") (pinfunction "GPIO3_35") (pintype "bidirectional"))
    )
    (net (code "94") (name "unconnected-(U2-GPIO4-Pad36)") (class "Default")
      (node (ref "U2") (pin "36") (pinfunction "GPIO4_36") (pintype "bidirectional"))
    )
    (net (code "95") (name "unconnected-(U2-GPIO5-Pad37)") (class "Default")
      (node (ref "U2") (pin "37") (pinfunction "GPIO5_37") (pintype "bidirectional"))
    )
    (net (code "96") (name "unconnected-(U2-GPIO6-Pad42)") (class "Default")
      (node (ref "U2") (pin "42") (pinfunction "GPIO6_42") (pintype "bidirectional"))
    )
    (net (code "97") (name "unconnected-(U2-GPIO7-Pad43)") (class "Default")
      (node (ref "U2") (pin "43") (pinfunction "GPIO7_43") (pintype "bidirectional"))
    )
    (net (code "98") (name "unconnected-(U2-NC-Pad18)") (class "Default")
      (node (ref "U2") (pin "18") (pinfunction "NC_18") (pintype "no_connect"))
    )
    (net (code "99") (name "unconnected-(U2-NC_2-Pad6)") (class "Default")
      (node (ref "U2") (pin "6") (pinfunction "NC_2_6") (pintype "no_connect"))
    )
    (net (code "100") (name "unconnected-(U2-NC_3-Pad7)") (class "Default")
      (node (ref "U2") (pin "7") (pinfunction "NC_3_7") (pintype "no_connect"))
    )
    (net (code "101") (name "unconnected-(U2-NC_4-Pad8)") (class "Default")
      (node (ref "U2") (pin "8") (pinfunction "NC_4_8") (pintype "no_connect"))
    )
    (net (code "102") (name "unconnected-(U2-NC_5-Pad9)") (class "Default")
      (node (ref "U2") (pin "9") (pinfunction "NC_5_9") (pintype "no_connect"))
    )
    (net (code "103") (name "unconnected-(U2-NC_6-Pad17)") (class "Default")
      (node (ref "U2") (pin "17") (pinfunction "NC_6_17") (pintype "no_connect"))
    )
    (net (code "104") (name "unconnected-(U2-PRTCTL3-Pad16)") (class "Default")
      (node (ref "U2") (pin "16") (pinfunction "PRTCTL3_16") (pintype "passive"))
    )
    (net (code "105") (name "unconnected-(U2-TDO-Pad31)") (class "Default")
      (node (ref "U2") (pin "31") (pinfunction "TDO_31") (pintype "passive"))
    )
    (net (code "106") (name "unconnected-(U2-TEST1-Pad13)") (class "Default")
      (node (ref "U2") (pin "13") (pinfunction "TEST1_13") (pintype "passive"))
    )
    (net (code "107") (name "unconnected-(U2-TEST4-Pad47)") (class "Default")
      (node (ref "U2") (pin "47") (pinfunction "TEST4_47") (pintype "passive"))
    )
    (net (code "108") (name "unconnected-(U2-USBDM3-Pad3)") (class "Default")
      (node (ref "U2") (pin "3") (pinfunction "USBDM3_3") (pintype "passive"))
    )
    (net (code "109") (name "unconnected-(U2-USBDP3-Pad4)") (class "Default")
      (node (ref "U2") (pin "4") (pinfunction "USBDP3_4") (pintype "passive"))
    )
    (net (code "110") (name "unconnected-(U4-USB_DN-Pad18)") (class "Default")
      (node (ref "U4") (pin "18") (pinfunction "USB_DN_18") (pintype "bidirectional"))
    )
    (net (code "111") (name "unconnected-(U4-USB_DP-Pad16)") (class "Default")
      (node (ref "U4") (pin "16") (pinfunction "USB_DP_16") (pintype "bidirectional"))
    )
    (net (code "112") (name "unconnected-(U4-USB_ID-Pad3)") (class "Default")
      (node (ref "U4") (pin "3") (pinfunction "USB_ID_3") (pintype "bidirectional"))
    )
  )
)
